# resonant-bp.net
KiCad netlist of a schematic drawn in EAGLE
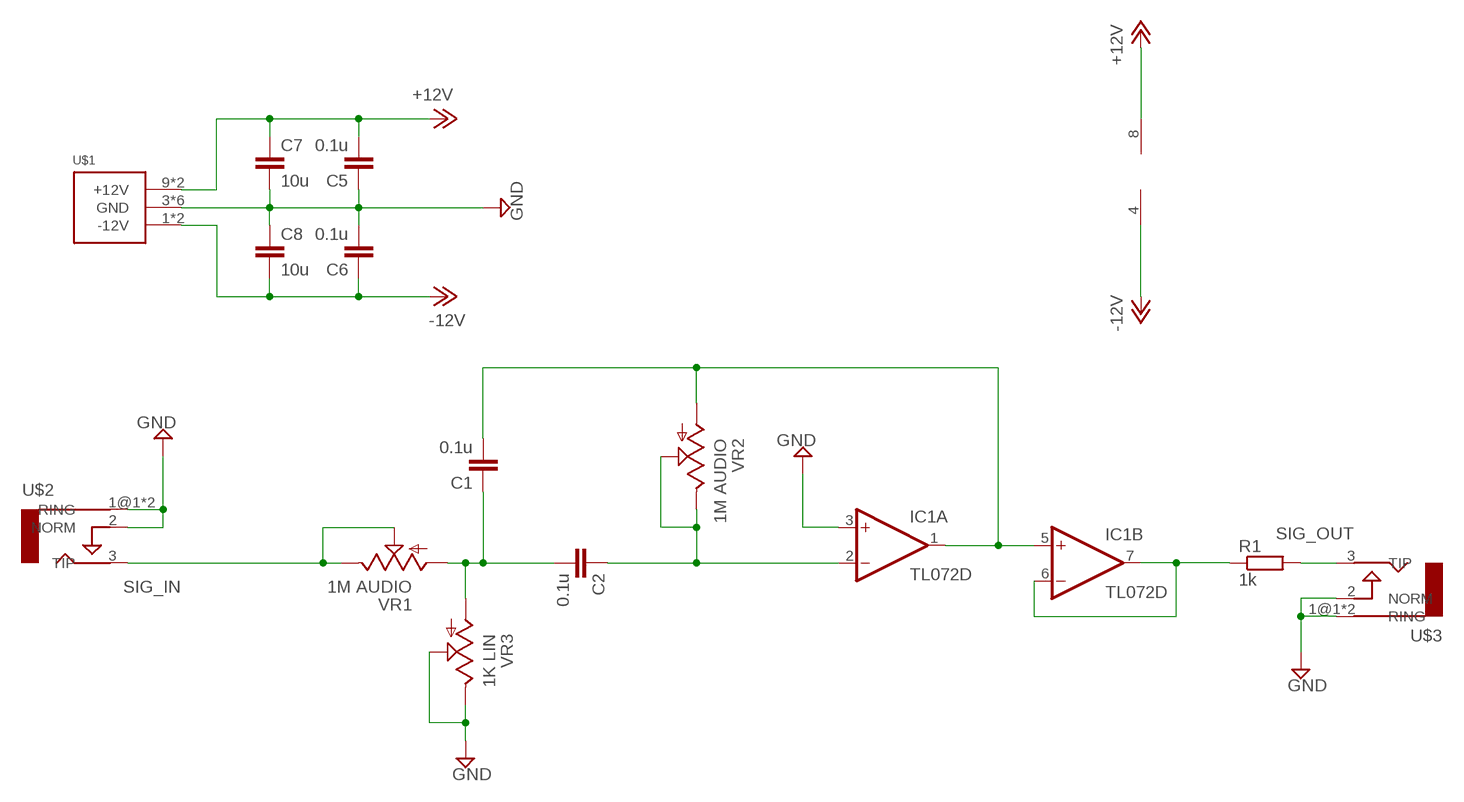
[diagram p0: schematic, sheet 1]

(export (version "E")
  (design (tool "Eeschema 10.0.6"))
  (components
    (comp (ref "C1")
      (value "0.1u")
      (footprint "eagle-import:C0805")
      (libsource (lib "eagle-import") (part "C-EUC0805"))
    )
    (comp (ref "C2")
      (value "0.1u")
      (footprint "eagle-import:C0805")
      (libsource (lib "eagle-import") (part "C-EUC0805"))
    )
    (comp (ref "C5")
      (value "0.1u")
      (footprint "eagle-import:C0805")
      (libsource (lib "eagle-import") (part "C-EUC0805"))
    )
    (comp (ref "C6")
      (value "0.1u")
      (footprint "eagle-import:C0805")
      (libsource (lib "eagle-import") (part "C-EUC0805"))
    )
    (comp (ref "C7")
      (value "10u")
      (footprint "eagle-import:C0805")
      (libsource (lib "eagle-import") (part "C-EUC0805"))
    )
    (comp (ref "C8")
      (value "10u")
      (footprint "eagle-import:C0805")
      (libsource (lib "eagle-import") (part "C-EUC0805"))
    )
    (comp (ref "IC1")
      (value "TL072D")
      (footprint "eagle-import:SO08")
      (libsource (lib "eagle-import") (part "TL072D"))
    )
    (comp (ref "R1")
      (value "1k")
      (footprint "eagle-import:R0805")
      (libsource (lib "eagle-import") (part "R-EU_R0805"))
    )
    (comp (ref "U$1")
      (value "POWER_SIMPLE10")
      (footprint "eagle-import:POWER_10")
      (libsource (lib "eagle-import") (part "POWER_SIMPLE10"))
    )
    (comp (ref "U$2")
      (value "AUDIO-JACKERTHENVAR")
      (footprint "eagle-import:ERTHENVAR-JACK")
      (libsource (lib "eagle-import") (part "AUDIO-JACKERTHENVAR"))
    )
    (comp (ref "U$3")
      (value "AUDIO-JACKERTHENVAR")
      (footprint "eagle-import:ERTHENVAR-JACK")
      (libsource (lib "eagle-import") (part "AUDIO-JACKERTHENVAR"))
    )
    (comp (ref "VR1")
      (value "1M AUDIO")
      (footprint "eagle-import:9MM_SNAP-IN_POT")
      (libsource (lib "eagle-import") (part "9MM_SNAP-IN_POT_"))
    )
    (comp (ref "VR2")
      (value "1M AUDIO")
      (footprint "eagle-import:9MM_SNAP-IN_POT")
      (libsource (lib "eagle-import") (part "9MM_SNAP-IN_POT_"))
    )
    (comp (ref "VR3")
      (value "1K LIN")
      (footprint "eagle-import:9MM_SNAP-IN_POT")
      (libsource (lib "eagle-import") (part "9MM_SNAP-IN_POT_"))
    )
  )
  (nets
    (net (code "1") (name "+12V") (class "Default")
      (node (ref "C5") (pin "2") (pinfunction "2_2") (pintype "passive"))
      (node (ref "C7") (pin "1") (pinfunction "1_1") (pintype "passive"))
      (node (ref "IC1") (pin "8") (pinfunction "V+_8") (pintype "power_in"))
      (node (ref "U$1") (pin "10") (pinfunction "+12V_10") (pintype "bidirectional"))
      (node (ref "U$1") (pin "9") (pinfunction "+12V_9") (pintype "bidirectional"))
    )
    (net (code "2") (name "-12V") (class "Default")
      (node (ref "C6") (pin "1") (pinfunction "1_1") (pintype "passive"))
      (node (ref "C8") (pin "2") (pinfunction "2_2") (pintype "passive"))
      (node (ref "IC1") (pin "4") (pinfunction "V-_4") (pintype "power_in"))
      (node (ref "U$1") (pin "1") (pinfunction "-12V_1") (pintype "bidirectional"))
      (node (ref "U$1") (pin "2") (pinfunction "-12V_2") (pintype "bidirectional"))
    )
    (net (code "3") (name "/SIG_IN") (class "Default")
      (node (ref "U$2") (pin "3") (pinfunction "TIP_3") (pintype "bidirectional"))
      (node (ref "VR1") (pin "2") (pinfunction "S_2") (pintype "passive"))
      (node (ref "VR1") (pin "3") (pinfunction "E_3") (pintype "passive"))
    )
    (net (code "4") (name "/SIG_OUT") (class "Default")
      (node (ref "R1") (pin "2") (pinfunction "2_2") (pintype "passive"))
      (node (ref "U$3") (pin "3") (pinfunction "TIP_3") (pintype "bidirectional"))
    )
    (net (code "5") (name "GND") (class "Default")
      (node (ref "C5") (pin "1") (pinfunction "1_1") (pintype "passive"))
      (node (ref "C6") (pin "2") (pinfunction "2_2") (pintype "passive"))
      (node (ref "C7") (pin "2") (pinfunction "2_2") (pintype "passive"))
      (node (ref "C8") (pin "1") (pinfunction "1_1") (pintype "passive"))
      (node (ref "IC1") (pin "3") (pinfunction "+IN_3") (pintype "input"))
      (node (ref "U$1") (pin "3") (pinfunction "GND_3") (pintype "bidirectional"))
      (node (ref "U$1") (pin "4") (pinfunction "GND_4") (pintype "bidirectional"))
      (node (ref "U$1") (pin "5") (pinfunction "GND_5") (pintype "bidirectional"))
      (node (ref "U$1") (pin "6") (pinfunction "GND_6") (pintype "bidirectional"))
      (node (ref "U$1") (pin "7") (pinfunction "GND_7") (pintype "bidirectional"))
      (node (ref "U$1") (pin "8") (pinfunction "GND_8") (pintype "bidirectional"))
      (node (ref "U$2") (pin "1@1") (pinfunction "RING_1@1") (pintype "bidirectional"))
      (node (ref "U$2") (pin "1@2") (pinfunction "RING_1@2") (pintype "bidirectional"))
      (node (ref "U$2") (pin "2") (pinfunction "NORM_2") (pintype "bidirectional"))
      (node (ref "U$3") (pin "1@1") (pinfunction "RING_1@1") (pintype "bidirectional"))
      (node (ref "U$3") (pin "1@2") (pinfunction "RING_1@2") (pintype "bidirectional"))
      (node (ref "U$3") (pin "2") (pinfunction "NORM_2") (pintype "bidirectional"))
      (node (ref "VR3") (pin "2") (pinfunction "S_2") (pintype "passive"))
      (node (ref "VR3") (pin "3") (pinfunction "E_3") (pintype "passive"))
    )
    (net (code "6") (name "Net-(IC1A--IN)") (class "Default")
      (node (ref "C2") (pin "1") (pinfunction "1_1") (pintype "passive"))
      (node (ref "IC1") (pin "2") (pinfunction "-IN_2") (pintype "input"))
      (node (ref "VR2") (pin "2") (pinfunction "S_2") (pintype "passive"))
      (node (ref "VR2") (pin "3") (pinfunction "E_3") (pintype "passive"))
    )
    (net (code "7") (name "Net-(IC1A-OUT)") (class "Default")
      (node (ref "C1") (pin "2") (pinfunction "2_2") (pintype "passive"))
      (node (ref "IC1") (pin "1") (pinfunction "OUT_1") (pintype "output"))
      (node (ref "IC1") (pin "5") (pinfunction "+IN_5") (pintype "input"))
      (node (ref "VR2") (pin "1") (pinfunction "A_1") (pintype "passive"))
    )
    (net (code "8") (name "Net-(IC1B--IN)") (class "Default")
      (node (ref "IC1") (pin "6") (pinfunction "-IN_6") (pintype "input"))
      (node (ref "IC1") (pin "7") (pinfunction "OUT_7") (pintype "output"))
      (node (ref "R1") (pin "1") (pinfunction "1_1") (pintype "passive"))
    )
    (net (code "9") (name "Net-(VR1-A)") (class "Default")
      (node (ref "C1") (pin "1") (pinfunction "1_1") (pintype "passive"))
      (node (ref "C2") (pin "2") (pinfunction "2_2") (pintype "passive"))
      (node (ref "VR1") (pin "1") (pinfunction "A_1") (pintype "passive"))
      (node (ref "VR3") (pin "1") (pinfunction "A_1") (pintype "passive"))
    )
  )
)
